# design.net
KiCad netlist of a schematic drawn in Altium Designer
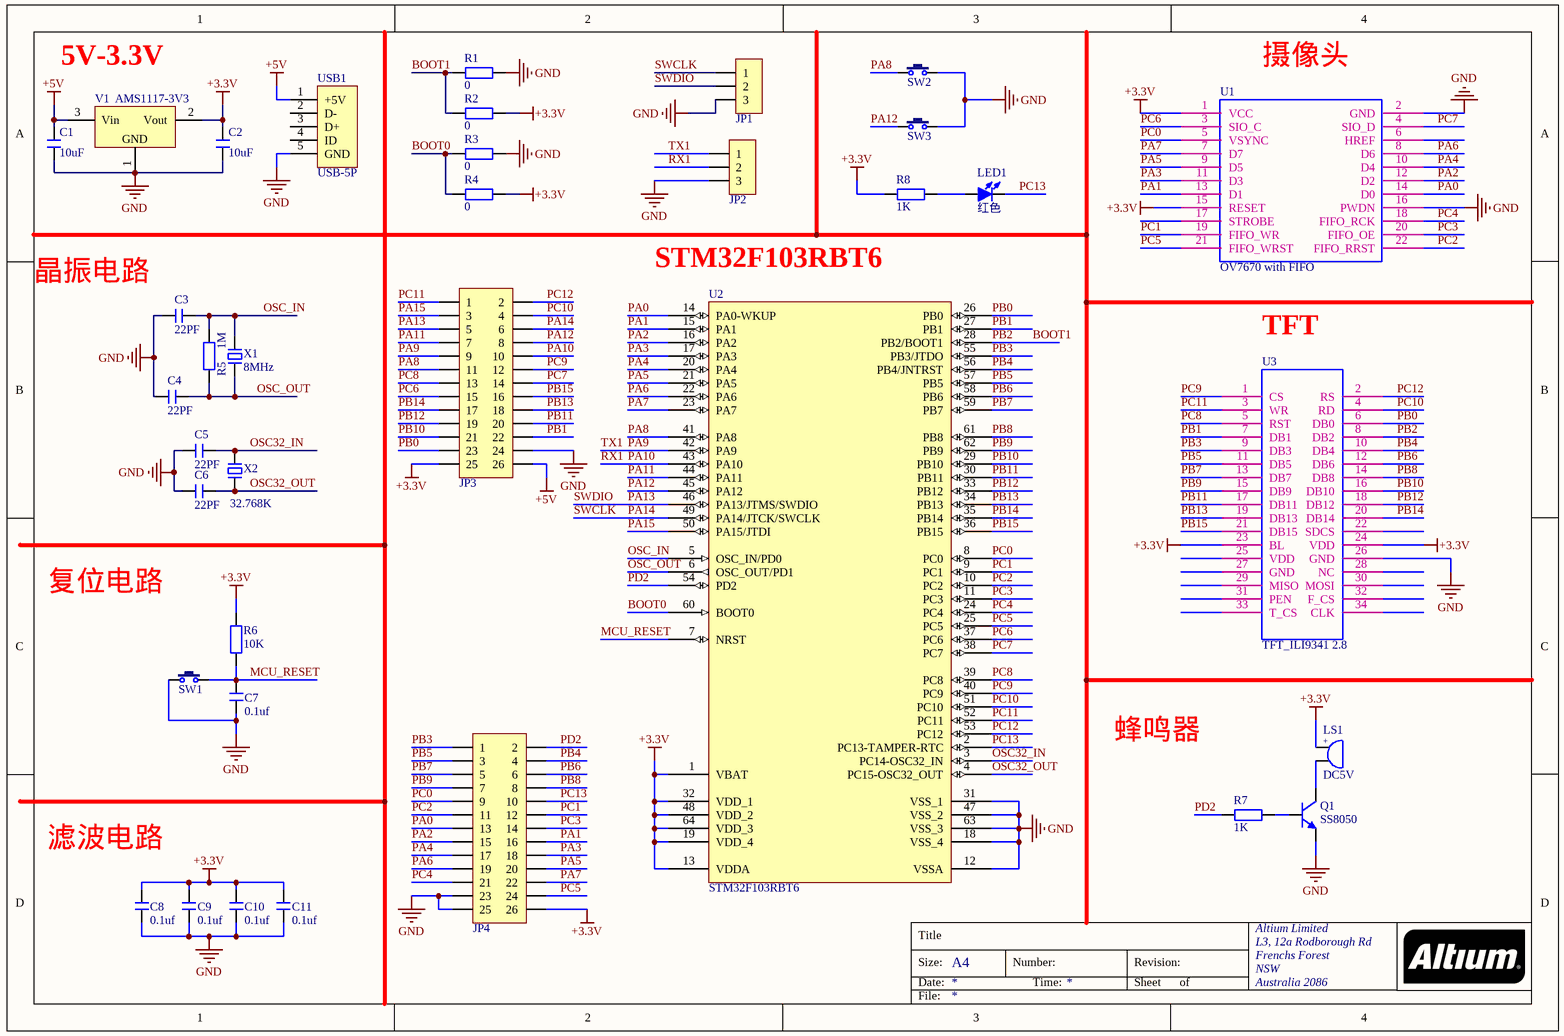
[diagram p0: 车牌识别.SchDoc]

(export (version "E")
  (design (tool "Eeschema 10.0.6"))
  (components
    (comp (ref "C1")
      (value "10uF")
      (footprint "C 0805_M")
      (description "无极性贴片电容")
      (fields (field (name "版权归属") "源创客"))
      (libsource (lib "3.1   - 电阻-电容-电感") (part "C"))
    )
    (comp (ref "C2")
      (value "10uF")
      (footprint "C 0805_M")
      (description "无极性贴片电容")
      (fields (field (name "版权归属") "源创客"))
      (libsource (lib "3.1   - 电阻-电容-电感") (part "C"))
    )
    (comp (ref "C3")
      (value "22PF")
      (footprint "C 0805_M")
      (description "无极性贴片电容")
      (fields (field (name "版权归属") "源创客"))
      (libsource (lib "3.1   - 电阻-电容-电感") (part "C"))
    )
    (comp (ref "C4")
      (value "22PF")
      (footprint "C 0805_M")
      (description "无极性贴片电容")
      (fields (field (name "版权归属") "源创客"))
      (libsource (lib "3.1   - 电阻-电容-电感") (part "C"))
    )
    (comp (ref "C5")
      (value "22PF")
      (footprint "C 0805_M")
      (description "无极性贴片电容")
      (fields (field (name "版权归属") "源创客"))
      (libsource (lib "3.1   - 电阻-电容-电感") (part "C"))
    )
    (comp (ref "C6")
      (value "22PF")
      (footprint "C 0805_M")
      (description "无极性贴片电容")
      (fields (field (name "版权归属") "源创客"))
      (libsource (lib "3.1   - 电阻-电容-电感") (part "C"))
    )
    (comp (ref "C7")
      (value "0.1uf")
      (footprint "C 0805_M")
      (description "无极性贴片电容")
      (fields (field (name "版权归属") "源创客"))
      (libsource (lib "3.1   - 电阻-电容-电感") (part "C"))
    )
    (comp (ref "C8")
      (value "0.1uf")
      (footprint "C 0805_M")
      (description "无极性贴片电容")
      (fields (field (name "版权归属") "源创客"))
      (libsource (lib "3.1   - 电阻-电容-电感") (part "C"))
    )
    (comp (ref "C9")
      (value "0.1uf")
      (footprint "C 0805_M")
      (description "无极性贴片电容")
      (fields (field (name "版权归属") "源创客"))
      (libsource (lib "3.1   - 电阻-电容-电感") (part "C"))
    )
    (comp (ref "C10")
      (value "0.1uf")
      (footprint "C 0805_M")
      (description "无极性贴片电容")
      (fields (field (name "版权归属") "源创客"))
      (libsource (lib "3.1   - 电阻-电容-电感") (part "C"))
    )
    (comp (ref "C11")
      (value "0.1uf")
      (footprint "C 0805_M")
      (description "无极性贴片电容")
      (fields (field (name "版权归属") "源创客"))
      (libsource (lib "3.1   - 电阻-电容-电感") (part "C"))
    )
    (comp (ref "JP1")
      (value "HDR-1X3")
      (footprint "HDR2.54-LI-3P")
      (description "3P接插件")
      (fields (field (name "版权归属") "源创客"))
      (libsource (lib "4.5   - 接插件-脚距2.54") (part "Header 3"))
    )
    (comp (ref "JP2")
      (value "HDR-1X3")
      (footprint "HDR2.54-LI-3P")
      (description "3P接插件")
      (fields (field (name "版权归属") "源创客"))
      (libsource (lib "4.5   - 接插件-脚距2.54") (part "Header 3"))
    )
    (comp (ref "JP3")
      (value "Header 2X11")
      (footprint "HDR2.54-LI-2x13P")
      (description "13*2P接插件")
      (fields (field (name "版权归属") "源创客"))
      (libsource (lib "4.5   - 接插件-脚距2.54") (part "Header 13X2"))
    )
    (comp (ref "JP4")
      (value "Header 2X11")
      (footprint "HDR2.54-LI-2x13P")
      (description "13*2P接插件")
      (fields (field (name "版权归属") "源创客"))
      (libsource (lib "4.5   - 接插件-脚距2.54") (part "Header 13X2"))
    )
    (comp (ref "LED1")
      (value "红色")
      (footprint "LED 0805W")
      (description "贴片LED")
      (fields (field (name "版权归属") "源创客"))
      (libsource (lib "9.1   - LED") (part "LED-SMD"))
    )
    (comp (ref "LS1")
      (value "DC5V")
      (footprint "BEEP 5x9x5.5")
      (description "蜂鸣器")
      (fields (field (name "版权归属") "源创客"))
      (libsource (lib "15.1 - 未分类器件") (part "BEEP"))
    )
    (comp (ref "Q1")
      (value "SS8050")
      (footprint "SOT23-3M")
      (description "高频放大-NPN型")
      (fields (field (name "版权归属") "源创客"))
      (libsource (lib "6.2   - 三极管") (part "8050-SMD"))
    )
    (comp (ref "R1")
      (value "0")
      (footprint "R 0805_M")
      (description "贴片电阻")
      (fields (field (name "版权归属") "源创客"))
      (libsource (lib "3.1   - 电阻-电容-电感") (part "R"))
    )
    (comp (ref "R2")
      (value "0")
      (footprint "R 0805_M")
      (description "贴片电阻")
      (fields (field (name "版权归属") "源创客"))
      (libsource (lib "3.1   - 电阻-电容-电感") (part "R"))
    )
    (comp (ref "R3")
      (value "0")
      (footprint "R 0805_M")
      (description "贴片电阻")
      (fields (field (name "版权归属") "源创客"))
      (libsource (lib "3.1   - 电阻-电容-电感") (part "R"))
    )
    (comp (ref "R4")
      (value "0")
      (footprint "R 0805_M")
      (description "贴片电阻")
      (fields (field (name "版权归属") "源创客"))
      (libsource (lib "3.1   - 电阻-电容-电感") (part "R"))
    )
    (comp (ref "R5")
      (value "1M")
      (footprint "R 0805_M")
      (description "贴片电阻")
      (fields (field (name "版权归属") "源创客"))
      (libsource (lib "3.1   - 电阻-电容-电感") (part "R"))
    )
    (comp (ref "R6")
      (value "10K")
      (footprint "R 0805_M")
      (description "贴片电阻")
      (fields (field (name "版权归属") "源创客"))
      (libsource (lib "3.1   - 电阻-电容-电感") (part "R"))
    )
    (comp (ref "R7")
      (value "1K")
      (footprint "R 0805_M")
      (description "贴片电阻")
      (fields (field (name "版权归属") "源创客"))
      (libsource (lib "3.1   - 电阻-电容-电感") (part "R"))
    )
    (comp (ref "R8")
      (value "1K")
      (footprint "R 0805_M")
      (description "贴片电阻")
      (fields (field (name "版权归属") "源创客"))
      (libsource (lib "3.1   - 电阻-电容-电感") (part "R"))
    )
    (comp (ref "SW1")
      (value "3x6x5")
      (footprint "TSW SMD-3*6*2.5")
      (description "3x6轻触开关")
      (fields (field (name "版权归属") "源创客"))
      (libsource (lib "5.1   - 按键-开关") (part "TSW 3x6"))
    )
    (comp (ref "SW2")
      (value "3x6x5")
      (footprint "TSW SMD-3*6*2.5")
      (description "3x6轻触开关")
      (fields (field (name "版权归属") "源创客"))
      (libsource (lib "5.1   - 按键-开关") (part "TSW 3x6"))
    )
    (comp (ref "SW3")
      (value "3x6x5")
      (footprint "TSW SMD-3*6*2.5")
      (description "3x6轻触开关")
      (fields (field (name "版权归属") "源创客"))
      (libsource (lib "5.1   - 按键-开关") (part "TSW 3x6"))
    )
    (comp (ref "U1")
      (value "OV7670 with FIFO")
      (footprint "OV7670模块")
      (description "FIFO")
      (fields (field (name "PUBLISHER") "Altium Limited"))
      (libsource (lib "15.1 - 未分类器件") (part "OV7670"))
    )
    (comp (ref "U2")
      (value "STM32F103RBT6")
      (footprint "LQFP64 10x10_M")
      (libsource (lib "2.1   - STM32系列单片机") (part "STM32F103RCT6"))
    )
    (comp (ref "U3")
      (value "TFT_ILI9341 2.8")
      (footprint "TFT-2.8")
      (description "ILI9341")
      (libsource (lib "9.2   - 显示器件") (part "TFT"))
    )
    (comp (ref "USB1")
      (value "USB-5P")
      (footprint "USB-MICRO_A")
      (description "微型USB母座")
      (fields (field (name "版权归属") "源创客"))
      (libsource (lib "4.1   - 接口类") (part "USB-5P"))
    )
    (comp (ref "V1")
      (value "AMS1117-3V3")
      (footprint "SOT223_M")
      (description "三端稳压芯片")
      (fields (field (name "版权归属") "源创客"))
      (libsource (lib "1.3   - 电源类芯片") (part "AMS1117"))
    )
    (comp (ref "X1")
      (value "8MHz")
      (footprint "OSC HC-49S")
      (description "2脚无源脚晶振")
      (fields (field (name "版权归属") "源创客"))
      (libsource (lib "10.1 - 保险丝-晶振") (part "XTAL-2P"))
    )
    (comp (ref "X2")
      (value "32.768K")
      (footprint "OSC 3215-2P")
      (description "2脚无源脚晶振")
      (fields (field (name "版权归属") "源创客"))
      (libsource (lib "10.1 - 保险丝-晶振") (part "XTAL-2P"))
    )
  )
  (nets
    (net (code "1") (name "+3.3V") (class "Default")
      (node (ref "C10") (pin "2") (pinfunction "2_2") (pintype "passive"))
      (node (ref "C11") (pin "2") (pinfunction "2_2") (pintype "passive"))
      (node (ref "C2") (pin "2") (pinfunction "2_2") (pintype "passive"))
      (node (ref "C8") (pin "2") (pinfunction "2_2") (pintype "passive"))
      (node (ref "C9") (pin "2") (pinfunction "2_2") (pintype "passive"))
      (node (ref "JP3") (pin "25") (pinfunction "25_25") (pintype "passive"))
      (node (ref "JP4") (pin "26") (pinfunction "26_26") (pintype "passive"))
      (node (ref "LS1") (pin "1") (pinfunction "1_1") (pintype "passive"))
      (node (ref "R2") (pin "2") (pinfunction "2_2") (pintype "passive"))
      (node (ref "R4") (pin "2") (pinfunction "2_2") (pintype "passive"))
      (node (ref "R6") (pin "2") (pinfunction "2_2") (pintype "passive"))
      (node (ref "R8") (pin "2") (pinfunction "2_2") (pintype "passive"))
      (node (ref "U1") (pin "1") (pinfunction "VCC_1") (pintype "passive"))
      (node (ref "U1") (pin "15") (pinfunction "RESET_15") (pintype "passive"))
      (node (ref "U2") (pin "1") (pinfunction "VBAT_1") (pintype "power_in"))
      (node (ref "U2") (pin "13") (pinfunction "VDDA_13") (pintype "power_in"))
      (node (ref "U2") (pin "19") (pinfunction "VDD_4_19") (pintype "power_in"))
      (node (ref "U2") (pin "32") (pinfunction "VDD_1_32") (pintype "power_in"))
      (node (ref "U2") (pin "48") (pinfunction "VDD_2_48") (pintype "power_in"))
      (node (ref "U2") (pin "64") (pinfunction "VDD_3_64") (pintype "power_in"))
      (node (ref "U3") (pin "23") (pinfunction "BL_23") (pintype "passive"))
      (node (ref "U3") (pin "24") (pinfunction "VDD_24") (pintype "passive"))
      (node (ref "V1") (pin "2") (pinfunction "Vout_2") (pintype "passive"))
    )
    (net (code "2") (name "+5V") (class "Default")
      (node (ref "C1") (pin "2") (pinfunction "2_2") (pintype "passive"))
      (node (ref "JP3") (pin "26") (pinfunction "26_26") (pintype "passive"))
      (node (ref "USB1") (pin "1") (pinfunction "+5V_1") (pintype "passive"))
      (node (ref "V1") (pin "3") (pinfunction "Vin_3") (pintype "passive"))
    )
    (net (code "3") (name "/BOOT0") (class "Default")
      (node (ref "R3") (pin "1") (pinfunction "1_1") (pintype "passive"))
      (node (ref "R4") (pin "1") (pinfunction "1_1") (pintype "passive"))
      (node (ref "U2") (pin "60") (pinfunction "BOOT0_60") (pintype "input"))
    )
    (net (code "4") (name "/BOOT1") (class "Default")
      (node (ref "R1") (pin "1") (pinfunction "1_1") (pintype "passive"))
      (node (ref "R2") (pin "1") (pinfunction "1_1") (pintype "passive"))
      (node (ref "U2") (pin "28") (pinfunction "PB2/BOOT1_28") (pintype "bidirectional"))
      (node (ref "U3") (pin "8") (pinfunction "DB2_8") (pintype "passive"))
    )
    (net (code "5") (name "/MCU_RESET") (class "Default")
      (node (ref "C7") (pin "2") (pinfunction "2_2") (pintype "passive"))
      (node (ref "R6") (pin "1") (pinfunction "1_1") (pintype "passive"))
      (node (ref "SW1") (pin "2") (pinfunction "2_2") (pintype "passive"))
      (node (ref "U2") (pin "7") (pinfunction "NRST_7") (pintype "bidirectional"))
    )
    (net (code "6") (name "/OSC32_IN") (class "Default")
      (node (ref "C5") (pin "2") (pinfunction "2_2") (pintype "passive"))
      (node (ref "U2") (pin "3") (pinfunction "PC14-OSC32_IN_3") (pintype "bidirectional"))
      (node (ref "X2") (pin "2") (pinfunction "2_2") (pintype "passive"))
    )
    (net (code "7") (name "/OSC32_OUT") (class "Default")
      (node (ref "C6") (pin "2") (pinfunction "2_2") (pintype "passive"))
      (node (ref "U2") (pin "4") (pinfunction "PC15-OSC32_OUT_4") (pintype "bidirectional"))
      (node (ref "X2") (pin "1") (pinfunction "1_1") (pintype "passive"))
    )
    (net (code "8") (name "/OSC_IN") (class "Default")
      (node (ref "C3") (pin "2") (pinfunction "2_2") (pintype "passive"))
      (node (ref "R5") (pin "1") (pinfunction "1_1") (pintype "passive"))
      (node (ref "U2") (pin "5") (pinfunction "OSC_IN/PD0_5") (pintype "input"))
      (node (ref "X1") (pin "2") (pinfunction "2_2") (pintype "passive"))
    )
    (net (code "9") (name "/OSC_OUT") (class "Default")
      (node (ref "C4") (pin "2") (pinfunction "2_2") (pintype "passive"))
      (node (ref "R5") (pin "2") (pinfunction "2_2") (pintype "passive"))
      (node (ref "U2") (pin "6") (pinfunction "OSC_OUT/PD1_6") (pintype "output"))
      (node (ref "X1") (pin "1") (pinfunction "1_1") (pintype "passive"))
    )
    (net (code "10") (name "/PA0") (class "Default")
      (node (ref "JP4") (pin "13") (pinfunction "13_13") (pintype "passive"))
      (node (ref "U1") (pin "14") (pinfunction "D0_14") (pintype "passive"))
      (node (ref "U2") (pin "14") (pinfunction "PA0-WKUP_14") (pintype "bidirectional"))
    )
    (net (code "11") (name "/PA1") (class "Default")
      (node (ref "JP4") (pin "16") (pinfunction "16_16") (pintype "passive"))
      (node (ref "U1") (pin "13") (pinfunction "D1_13") (pintype "passive"))
      (node (ref "U2") (pin "15") (pinfunction "PA1_15") (pintype "bidirectional"))
    )
    (net (code "12") (name "/PA2") (class "Default")
      (node (ref "JP4") (pin "15") (pinfunction "15_15") (pintype "passive"))
      (node (ref "U1") (pin "12") (pinfunction "D2_12") (pintype "passive"))
      (node (ref "U2") (pin "16") (pinfunction "PA2_16") (pintype "bidirectional"))
    )
    (net (code "13") (name "/PA3") (class "Default")
      (node (ref "JP4") (pin "18") (pinfunction "18_18") (pintype "passive"))
      (node (ref "U1") (pin "11") (pinfunction "D3_11") (pintype "passive"))
      (node (ref "U2") (pin "17") (pinfunction "PA3_17") (pintype "bidirectional"))
    )
    (net (code "14") (name "/PA4") (class "Default")
      (node (ref "JP4") (pin "17") (pinfunction "17_17") (pintype "passive"))
      (node (ref "U1") (pin "10") (pinfunction "D4_10") (pintype "passive"))
      (node (ref "U2") (pin "20") (pinfunction "PA4_20") (pintype "bidirectional"))
    )
    (net (code "15") (name "/PA5") (class "Default")
      (node (ref "JP4") (pin "20") (pinfunction "20_20") (pintype "passive"))
      (node (ref "U1") (pin "9") (pinfunction "D5_9") (pintype "passive"))
      (node (ref "U2") (pin "21") (pinfunction "PA5_21") (pintype "bidirectional"))
    )
    (net (code "16") (name "/PA6") (class "Default")
      (node (ref "JP4") (pin "19") (pinfunction "19_19") (pintype "passive"))
      (node (ref "U1") (pin "8") (pinfunction "D6_8") (pintype "passive"))
      (node (ref "U2") (pin "22") (pinfunction "PA6_22") (pintype "bidirectional"))
    )
    (net (code "17") (name "/PA7") (class "Default")
      (node (ref "JP4") (pin "22") (pinfunction "22_22") (pintype "passive"))
      (node (ref "U1") (pin "7") (pinfunction "D7_7") (pintype "passive"))
      (node (ref "U2") (pin "23") (pinfunction "PA7_23") (pintype "bidirectional"))
    )
    (net (code "18") (name "/PA8") (class "Default")
      (node (ref "JP3") (pin "11") (pinfunction "11_11") (pintype "passive"))
      (node (ref "SW2") (pin "1") (pinfunction "1_1") (pintype "passive"))
      (node (ref "U2") (pin "41") (pinfunction "PA8_41") (pintype "bidirectional"))
    )
    (net (code "19") (name "/PA9") (class "Default")
      (node (ref "JP2") (pin "1") (pinfunction "1_1") (pintype "passive"))
      (node (ref "JP3") (pin "9") (pinfunction "9_9") (pintype "passive"))
      (node (ref "U2") (pin "42") (pinfunction "PA9_42") (pintype "bidirectional"))
    )
    (net (code "20") (name "/PA10") (class "Default")
      (node (ref "JP2") (pin "2") (pinfunction "2_2") (pintype "passive"))
      (node (ref "JP3") (pin "10") (pinfunction "10_10") (pintype "passive"))
      (node (ref "U2") (pin "43") (pinfunction "PA10_43") (pintype "bidirectional"))
    )
    (net (code "21") (name "/PA11") (class "Default")
      (node (ref "JP3") (pin "7") (pinfunction "7_7") (pintype "passive"))
      (node (ref "U2") (pin "44") (pinfunction "PA11_44") (pintype "bidirectional"))
    )
    (net (code "22") (name "/PA12") (class "Default")
      (node (ref "JP3") (pin "8") (pinfunction "8_8") (pintype "passive"))
      (node (ref "SW3") (pin "1") (pinfunction "1_1") (pintype "passive"))
      (node (ref "U2") (pin "45") (pinfunction "PA12_45") (pintype "bidirectional"))
    )
    (net (code "23") (name "/PA13") (class "Default")
      (node (ref "JP1") (pin "2") (pinfunction "2_2") (pintype "passive"))
      (node (ref "JP3") (pin "5") (pinfunction "5_5") (pintype "passive"))
      (node (ref "U2") (pin "46") (pinfunction "PA13/JTMS/SWDIO_46") (pintype "bidirectional"))
    )
    (net (code "24") (name "/PA14") (class "Default")
      (node (ref "JP1") (pin "1") (pinfunction "1_1") (pintype "passive"))
      (node (ref "JP3") (pin "6") (pinfunction "6_6") (pintype "passive"))
      (node (ref "U2") (pin "49") (pinfunction "PA14/JTCK/SWCLK_49") (pintype "bidirectional"))
    )
    (net (code "25") (name "/PA15") (class "Default")
      (node (ref "JP3") (pin "3") (pinfunction "3_3") (pintype "passive"))
      (node (ref "U2") (pin "50") (pinfunction "PA15/JTDI_50") (pintype "bidirectional"))
    )
    (net (code "26") (name "/PB0") (class "Default")
      (node (ref "JP3") (pin "23") (pinfunction "23_23") (pintype "passive"))
      (node (ref "U2") (pin "26") (pinfunction "PB0_26") (pintype "bidirectional"))
      (node (ref "U3") (pin "6") (pinfunction "DB0_6") (pintype "passive"))
    )
    (net (code "27") (name "/PB1") (class "Default")
      (node (ref "JP3") (pin "22") (pinfunction "22_22") (pintype "passive"))
      (node (ref "U2") (pin "27") (pinfunction "PB1_27") (pintype "bidirectional"))
      (node (ref "U3") (pin "7") (pinfunction "DB1_7") (pintype "passive"))
    )
    (net (code "28") (name "/PB3") (class "Default")
      (node (ref "JP4") (pin "1") (pinfunction "1_1") (pintype "passive"))
      (node (ref "U2") (pin "55") (pinfunction "PB3/JTDO_55") (pintype "bidirectional"))
      (node (ref "U3") (pin "9") (pinfunction "DB3_9") (pintype "passive"))
    )
    (net (code "29") (name "/PB4") (class "Default")
      (node (ref "JP4") (pin "4") (pinfunction "4_4") (pintype "passive"))
      (node (ref "U2") (pin "56") (pinfunction "PB4/JNTRST_56") (pintype "bidirectional"))
      (node (ref "U3") (pin "10") (pinfunction "DB4_10") (pintype "passive"))
    )
    (net (code "30") (name "/PB5") (class "Default")
      (node (ref "JP4") (pin "3") (pinfunction "3_3") (pintype "passive"))
      (node (ref "U2") (pin "57") (pinfunction "PB5_57") (pintype "bidirectional"))
      (node (ref "U3") (pin "11") (pinfunction "DB5_11") (pintype "passive"))
    )
    (net (code "31") (name "/PB6") (class "Default")
      (node (ref "JP4") (pin "6") (pinfunction "6_6") (pintype "passive"))
      (node (ref "U2") (pin "58") (pinfunction "PB6_58") (pintype "bidirectional"))
      (node (ref "U3") (pin "12") (pinfunction "DB6_12") (pintype "passive"))
    )
    (net (code "32") (name "/PB7") (class "Default")
      (node (ref "JP4") (pin "5") (pinfunction "5_5") (pintype "passive"))
      (node (ref "U2") (pin "59") (pinfunction "PB7_59") (pintype "bidirectional"))
      (node (ref "U3") (pin "13") (pinfunction "DB7_13") (pintype "passive"))
    )
    (net (code "33") (name "/PB8") (class "Default")
      (node (ref "JP4") (pin "8") (pinfunction "8_8") (pintype "passive"))
      (node (ref "U2") (pin "61") (pinfunction "PB8_61") (pintype "bidirectional"))
      (node (ref "U3") (pin "14") (pinfunction "DB8_14") (pintype "passive"))
    )
    (net (code "34") (name "/PB9") (class "Default")
      (node (ref "JP4") (pin "7") (pinfunction "7_7") (pintype "passive"))
      (node (ref "U2") (pin "62") (pinfunction "PB9_62") (pintype "bidirectional"))
      (node (ref "U3") (pin "15") (pinfunction "DB9_15") (pintype "passive"))
    )
    (net (code "35") (name "/PB10") (class "Default")
      (node (ref "JP3") (pin "21") (pinfunction "21_21") (pintype "passive"))
      (node (ref "U2") (pin "29") (pinfunction "PB10_29") (pintype "bidirectional"))
      (node (ref "U3") (pin "16") (pinfunction "DB10_16") (pintype "passive"))
    )
    (net (code "36") (name "/PB11") (class "Default")
      (node (ref "JP3") (pin "20") (pinfunction "20_20") (pintype "passive"))
      (node (ref "U2") (pin "30") (pinfunction "PB11_30") (pintype "bidirectional"))
      (node (ref "U3") (pin "17") (pinfunction "DB11_17") (pintype "passive"))
    )
    (net (code "37") (name "/PB12") (class "Default")
      (node (ref "JP3") (pin "19") (pinfunction "19_19") (pintype "passive"))
      (node (ref "U2") (pin "33") (pinfunction "PB12_33") (pintype "bidirectional"))
      (node (ref "U3") (pin "18") (pinfunction "DB12_18") (pintype "passive"))
    )
    (net (code "38") (name "/PB13") (class "Default")
      (node (ref "JP3") (pin "18") (pinfunction "18_18") (pintype "passive"))
      (node (ref "U2") (pin "34") (pinfunction "PB13_34") (pintype "bidirectional"))
      (node (ref "U3") (pin "19") (pinfunction "DB13_19") (pintype "passive"))
    )
    (net (code "39") (name "/PB14") (class "Default")
      (node (ref "JP3") (pin "17") (pinfunction "17_17") (pintype "passive"))
      (node (ref "U2") (pin "35") (pinfunction "PB14_35") (pintype "bidirectional"))
      (node (ref "U3") (pin "20") (pinfunction "DB14_20") (pintype "passive"))
    )
    (net (code "40") (name "/PB15") (class "Default")
      (node (ref "JP3") (pin "16") (pinfunction "16_16") (pintype "passive"))
      (node (ref "U2") (pin "36") (pinfunction "PB15_36") (pintype "bidirectional"))
      (node (ref "U3") (pin "21") (pinfunction "DB15_21") (pintype "passive"))
    )
    (net (code "41") (name "/PC0") (class "Default")
      (node (ref "JP4") (pin "9") (pinfunction "9_9") (pintype "passive"))
      (node (ref "U1") (pin "5") (pinfunction "VSYNC_5") (pintype "passive"))
      (node (ref "U2") (pin "8") (pinfunction "PC0_8") (pintype "bidirectional"))
    )
    (net (code "42") (name "/PC1") (class "Default")
      (node (ref "JP4") (pin "12") (pinfunction "12_12") (pintype "passive"))
      (node (ref "U1") (pin "19") (pinfunction "FIFO_WR_19") (pintype "passive"))
      (node (ref "U2") (pin "9") (pinfunction "PC1_9") (pintype "bidirectional"))
    )
    (net (code "43") (name "/PC2") (class "Default")
      (node (ref "JP4") (pin "11") (pinfunction "11_11") (pintype "passive"))
      (node (ref "U1") (pin "22") (pinfunction "FIFO_RRST_22") (pintype "passive"))
      (node (ref "U2") (pin "10") (pinfunction "PC2_10") (pintype "bidirectional"))
    )
    (net (code "44") (name "/PC3") (class "Default")
      (node (ref "JP4") (pin "14") (pinfunction "14_14") (pintype "passive"))
      (node (ref "U1") (pin "20") (pinfunction "FIFO_OE_20") (pintype "passive"))
      (node (ref "U2") (pin "11") (pinfunction "PC3_11") (pintype "bidirectional"))
    )
    (net (code "45") (name "/PC4") (class "Default")
      (node (ref "JP4") (pin "21") (pinfunction "21_21") (pintype "passive"))
      (node (ref "U1") (pin "18") (pinfunction "FIFO_RCK_18") (pintype "passive"))
      (node (ref "U2") (pin "24") (pinfunction "PC4_24") (pintype "bidirectional"))
    )
    (net (code "46") (name "/PC5") (class "Default")
      (node (ref "JP4") (pin "24") (pinfunction "24_24") (pintype "passive"))
      (node (ref "U1") (pin "21") (pinfunction "FIFO_WRST_21") (pintype "passive"))
      (node (ref "U2") (pin "25") (pinfunction "PC5_25") (pintype "bidirectional"))
    )
    (net (code "47") (name "/PC6") (class "Default")
      (node (ref "JP3") (pin "15") (pinfunction "15_15") (pintype "passive"))
      (node (ref "U1") (pin "3") (pinfunction "SIO_C_3") (pintype "passive"))
      (node (ref "U2") (pin "37") (pinfunction "PC6_37") (pintype "bidirectional"))
    )
    (net (code "48") (name "/PC7") (class "Default")
      (node (ref "JP3") (pin "14") (pinfunction "14_14") (pintype "passive"))
      (node (ref "U1") (pin "4") (pinfunction "SIO_D_4") (pintype "passive"))
      (node (ref "U2") (pin "38") (pinfunction "PC7_38") (pintype "bidirectional"))
    )
    (net (code "49") (name "/PC8") (class "Default")
      (node (ref "JP3") (pin "13") (pinfunction "13_13") (pintype "passive"))
      (node (ref "U2") (pin "39") (pinfunction "PC8_39") (pintype "bidirectional"))
      (node (ref "U3") (pin "5") (pinfunction "RST_5") (pintype "passive"))
    )
    (net (code "50") (name "/PC9") (class "Default")
      (node (ref "JP3") (pin "12") (pinfunction "12_12") (pintype "passive"))
      (node (ref "U2") (pin "40") (pinfunction "PC9_40") (pintype "bidirectional"))
      (node (ref "U3") (pin "1") (pinfunction "CS_1") (pintype "passive"))
    )
    (net (code "51") (name "/PC10") (class "Default")
      (node (ref "JP3") (pin "4") (pinfunction "4_4") (pintype "passive"))
      (node (ref "U2") (pin "51") (pinfunction "PC10_51") (pintype "bidirectional"))
      (node (ref "U3") (pin "4") (pinfunction "RD_4") (pintype "passive"))
    )
    (net (code "52") (name "/PC11") (class "Default")
      (node (ref "JP3") (pin "1") (pinfunction "1_1") (pintype "passive"))
      (node (ref "U2") (pin "52") (pinfunction "PC11_52") (pintype "bidirectional"))
      (node (ref "U3") (pin "3") (pinfunction "WR_3") (pintype "passive"))
    )
    (net (code "53") (name "/PC12") (class "Default")
      (node (ref "JP3") (pin "2") (pinfunction "2_2") (pintype "passive"))
      (node (ref "U2") (pin "53") (pinfunction "PC12_53") (pintype "bidirectional"))
      (node (ref "U3") (pin "2") (pinfunction "RS_2") (pintype "passive"))
    )
    (net (code "54") (name "/PC13") (class "Default")
      (node (ref "JP4") (pin "10") (pinfunction "10_10") (pintype "passive"))
      (node (ref "LED1") (pin "2") (pinfunction "K_2") (pintype "passive"))
      (node (ref "U2") (pin "2") (pinfunction "PC13-TAMPER-RTC_2") (pintype "bidirectional"))
    )
    (net (code "55") (name "/PD2") (class "Default")
      (node (ref "JP4") (pin "2") (pinfunction "2_2") (pintype "passive"))
      (node (ref "R7") (pin "2") (pinfunction "2_2") (pintype "passive"))
      (node (ref "U2") (pin "54") (pinfunction "PD2_54") (pintype "bidirectional"))
    )
    (net (code "56") (name "GND") (class "Default")
      (node (ref "C1") (pin "1") (pinfunction "1_1") (pintype "passive"))
      (node (ref "C10") (pin "1") (pinfunction "1_1") (pintype "passive"))
      (node (ref "C11") (pin "1") (pinfunction "1_1") (pintype "passive"))
      (node (ref "C2") (pin "1") (pinfunction "1_1") (pintype "passive"))
      (node (ref "C3") (pin "1") (pinfunction "1_1") (pintype "passive"))
      (node (ref "C4") (pin "1") (pinfunction "1_1") (pintype "passive"))
      (node (ref "C5") (pin "1") (pinfunction "1_1") (pintype "passive"))
      (node (ref "C6") (pin "1") (pinfunction "1_1") (pintype "passive"))
      (node (ref "C7") (pin "1") (pinfunction "1_1") (pintype "passive"))
      (node (ref "C8") (pin "1") (pinfunction "1_1") (pintype "passive"))
      (node (ref "C9") (pin "1") (pinfunction "1_1") (pintype "passive"))
      (node (ref "JP1") (pin "3") (pinfunction "3_3") (pintype "passive"))
      (node (ref "JP2") (pin "3") (pinfunction "3_3") (pintype "passive"))
      (node (ref "JP3") (pin "24") (pinfunction "24_24") (pintype "passive"))
      (node (ref "JP4") (pin "23") (pinfunction "23_23") (pintype "passive"))
      (node (ref "JP4") (pin "25") (pinfunction "25_25") (pintype "passive"))
      (node (ref "Q1") (pin "2") (pinfunction "E_2") (pintype "passive"))
      (node (ref "R1") (pin "2") (pinfunction "2_2") (pintype "passive"))
      (node (ref "R3") (pin "2") (pinfunction "2_2") (pintype "passive"))
      (node (ref "SW1") (pin "1") (pinfunction "1_1") (pintype "passive"))
      (node (ref "SW2") (pin "2") (pinfunction "2_2") (pintype "passive"))
      (node (ref "SW3") (pin "2") (pinfunction "2_2") (pintype "passive"))
      (node (ref "U1") (pin "16") (pinfunction "PWDN_16") (pintype "passive"))
      (node (ref "U1") (pin "2") (pinfunction "GND_2") (pintype "passive"))
      (node (ref "U2") (pin "12") (pinfunction "VSSA_12") (pintype "power_in"))
      (node (ref "U2") (pin "18") (pinfunction "VSS_4_18") (pintype "power_in"))
      (node (ref "U2") (pin "31") (pinfunction "VSS_1_31") (pintype "power_in"))
      (node (ref "U2") (pin "47") (pinfunction "VSS_2_47") (pintype "power_in"))
      (node (ref "U2") (pin "63") (pinfunction "VSS_3_63") (pintype "power_in"))
      (node (ref "U3") (pin "26") (pinfunction "GND_26") (pintype "passive"))
      (node (ref "USB1") (pin "5") (pinfunction "GND_5") (pintype "passive"))
      (node (ref "V1") (pin "1") (pinfunction "GND_1") (pintype "passive"))
    )
    (net (code "57") (name "Net-(LED1-A)") (class "Default")
      (node (ref "LED1") (pin "1") (pinfunction "A_1") (pintype "passive"))
      (node (ref "R8") (pin "1") (pinfunction "1_1") (pintype "passive"))
    )
    (net (code "58") (name "Net-(Q1-B)") (class "Default")
      (node (ref "Q1") (pin "1") (pinfunction "B_1") (pintype "passive"))
      (node (ref "R7") (pin "1") (pinfunction "1_1") (pintype "passive"))
    )
    (net (code "59") (name "Net-(Q1-C)") (class "Default")
      (node (ref "LS1") (pin "2") (pinfunction "2_2") (pintype "passive"))
      (node (ref "Q1") (pin "3") (pinfunction "C_3") (pintype "passive"))
    )
    (net (code "60") (name "unconnected-(U1-HREF-Pad6)") (class "Default")
      (node (ref "U1") (pin "6") (pinfunction "HREF_6") (pintype "passive"))
    )
    (net (code "61") (name "unconnected-(U1-STROBE-Pad17)") (class "Default")
      (node (ref "U1") (pin "17") (pinfunction "STROBE_17") (pintype "passive"))
    )
    (net (code "62") (name "unconnected-(U3-CLK-Pad34)") (class "Default")
      (node (ref "U3") (pin "34") (pinfunction "CLK_34") (pintype "passive"))
    )
    (net (code "63") (name "unconnected-(U3-F_CS-Pad32)") (class "Default")
      (node (ref "U3") (pin "32") (pinfunction "F_CS_32") (pintype "passive"))
    )
    (net (code "64") (name "unconnected-(U3-GND-Pad27)") (class "Default")
      (node (ref "U3") (pin "27") (pinfunction "GND_27") (pintype "passive"))
    )
    (net (code "65") (name "unconnected-(U3-MISO-Pad29)") (class "Default")
      (node (ref "U3") (pin "29") (pinfunction "MISO_29") (pintype "passive"))
    )
    (net (code "66") (name "unconnected-(U3-MOSI-Pad30)") (class "Default")
      (node (ref "U3") (pin "30") (pinfunction "MOSI_30") (pintype "passive"))
    )
    (net (code "67") (name "unconnected-(U3-NC-Pad28)") (class "Default")
      (node (ref "U3") (pin "28") (pinfunction "NC_28") (pintype "passive"))
    )
    (net (code "68") (name "unconnected-(U3-PEN-Pad31)") (class "Default")
      (node (ref "U3") (pin "31") (pinfunction "PEN_31") (pintype "passive"))
    )
    (net (code "69") (name "unconnected-(U3-SDCS-Pad22)") (class "Default")
      (node (ref "U3") (pin "22") (pinfunction "SDCS_22") (pintype "passive"))
    )
    (net (code "70") (name "unconnected-(U3-T_CS-Pad33)") (class "Default")
      (node (ref "U3") (pin "33") (pinfunction "T_CS_33") (pintype "passive"))
    )
    (net (code "71") (name "unconnected-(U3-VDD-Pad25)") (class "Default")
      (node (ref "U3") (pin "25") (pinfunction "VDD_25") (pintype "passive"))
    )
    (net (code "72") (name "unconnected-(USB1-D+-Pad3)") (class "Default")
      (node (ref "USB1") (pin "3") (pinfunction "D+_3") (pintype "passive"))
    )
    (net (code "73") (name "unconnected-(USB1-D--Pad2)") (class "Default")
      (node (ref "USB1") (pin "2") (pinfunction "D-_2") (pintype "passive"))
    )
    (net (code "74") (name "unconnected-(USB1-ID-Pad4)") (class "Default")
      (node (ref "USB1") (pin "4") (pinfunction "ID_4") (pintype "passive"))
    )
  )
)
